# SCH_hiiiiibrahim_2025-10-19.net
KiCad netlist of a schematic drawn in EasyEDA
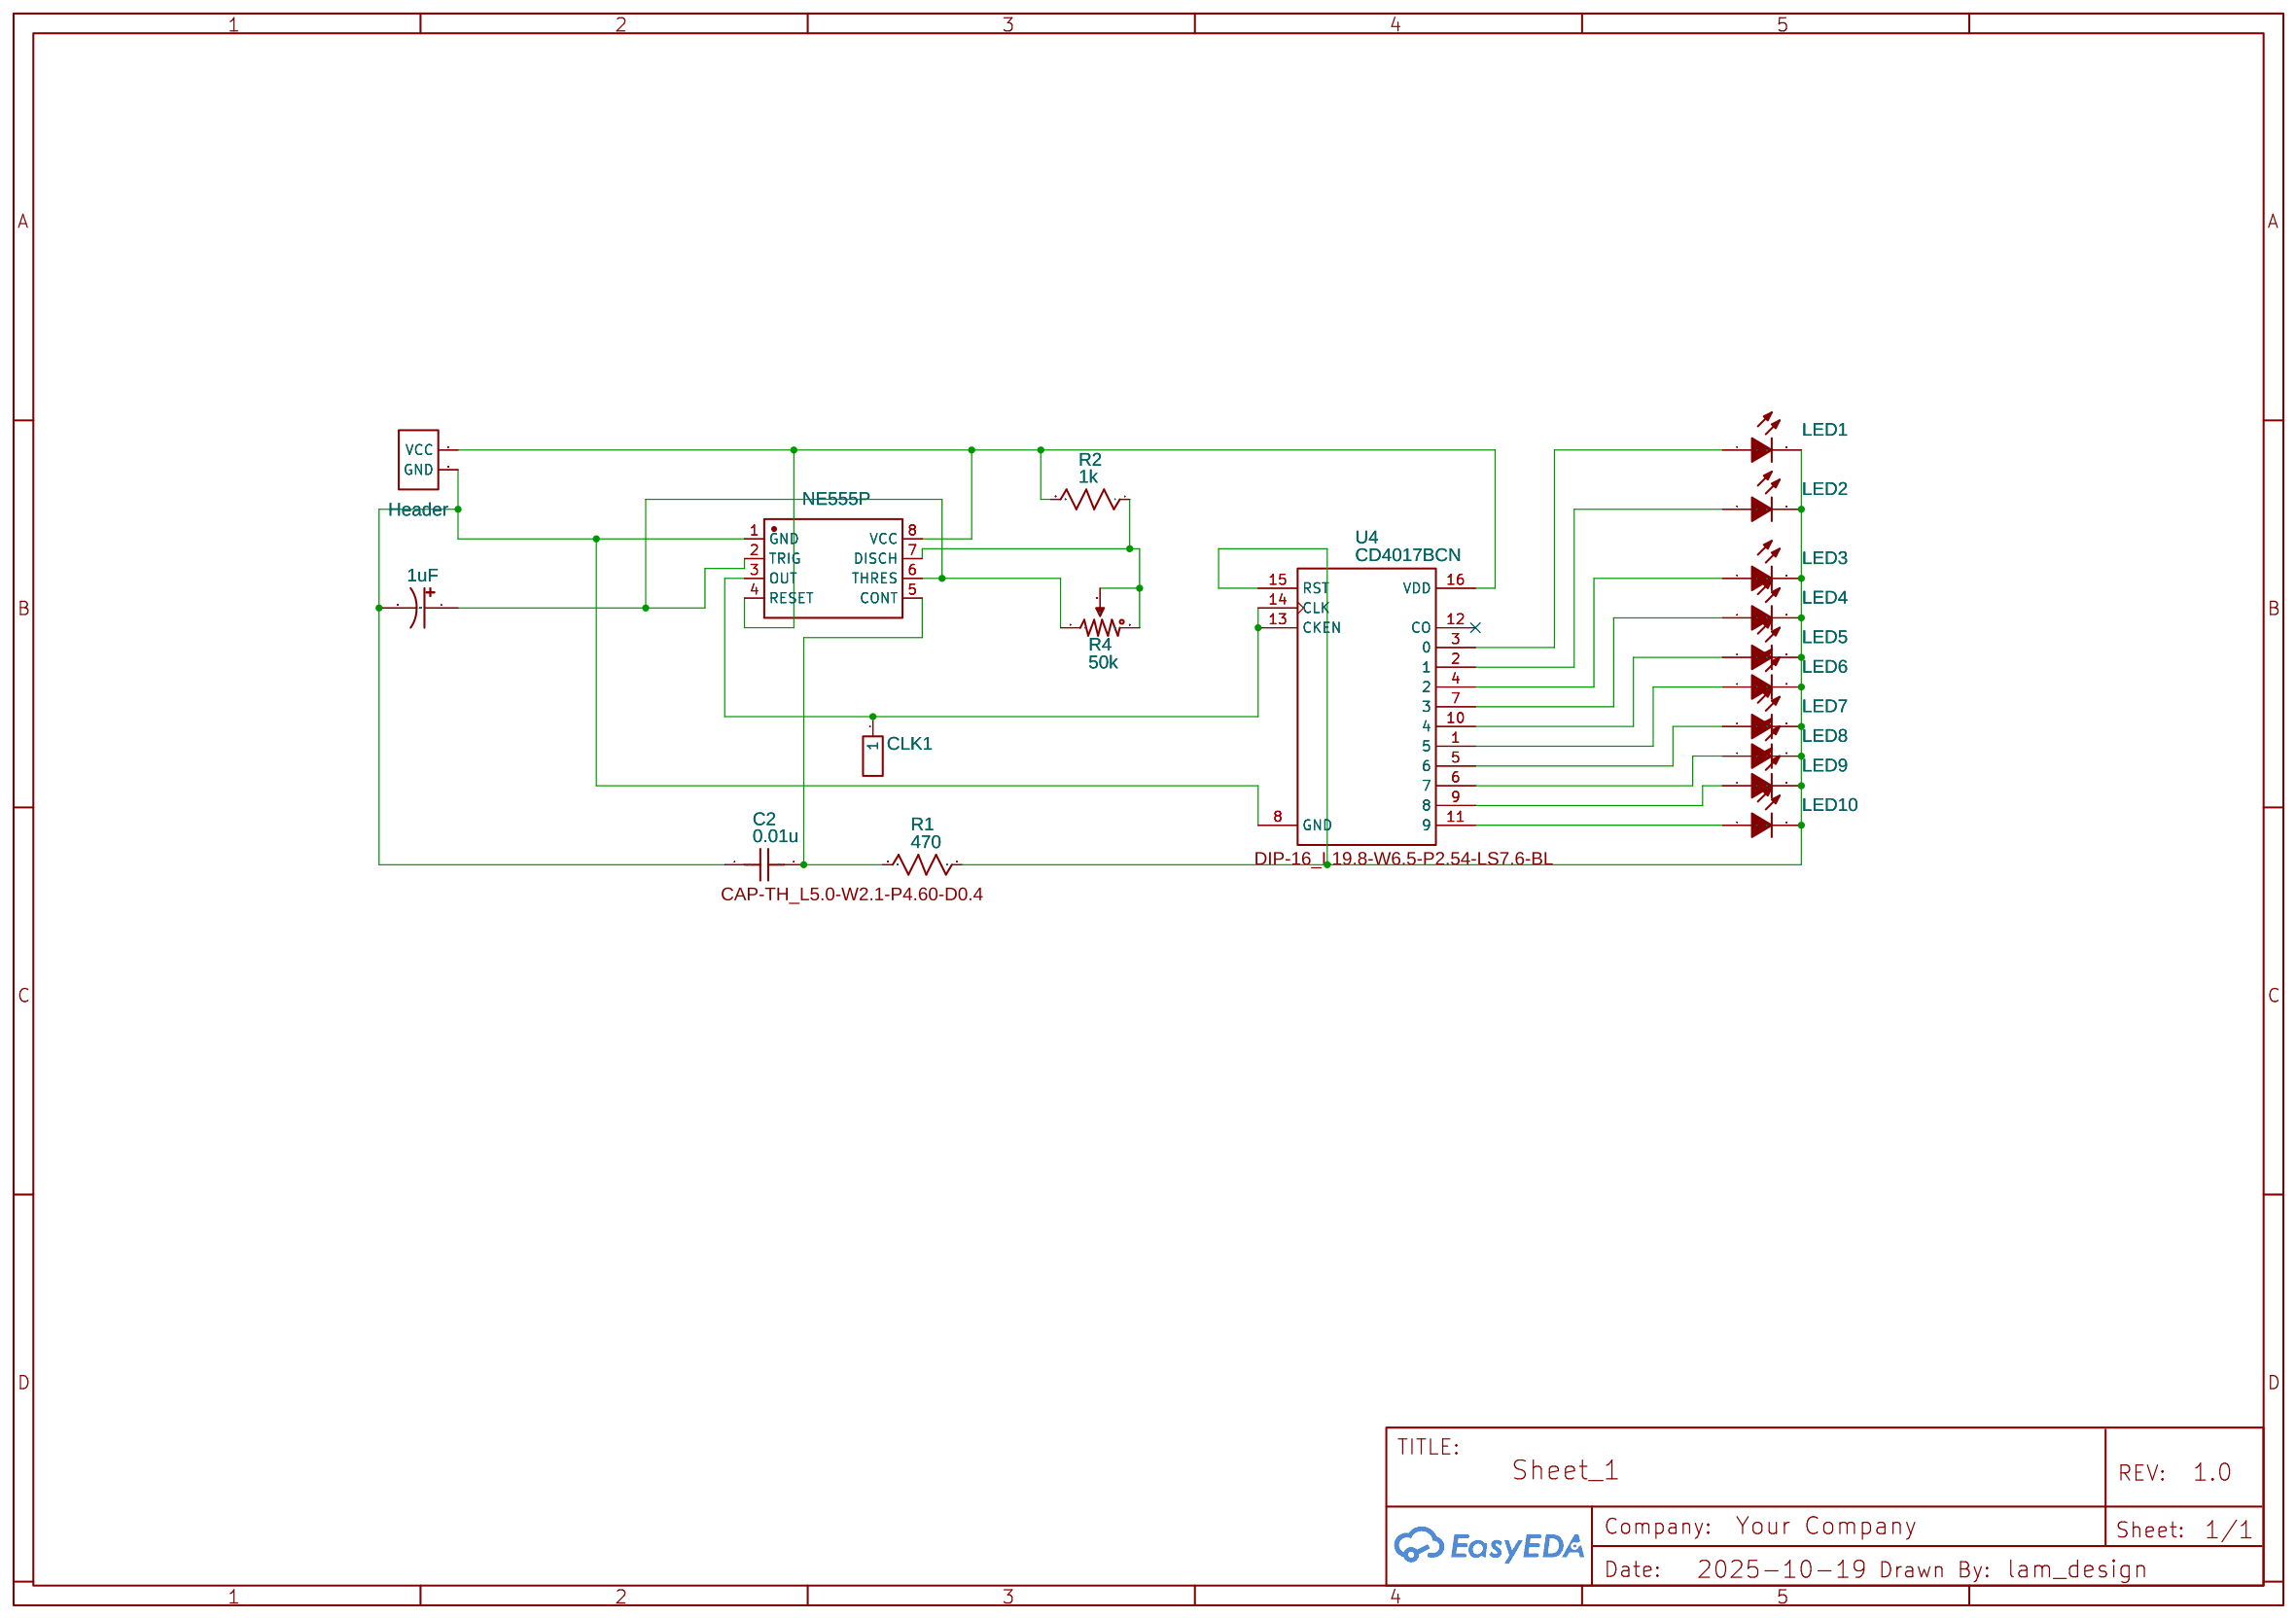
[diagram p0: schematic sheet]

(export (version "E")
  (design (tool "Eeschema 10.0.6"))
  (components
    (comp (ref "C1")
      (value "1uF")
      (fields (field (name "Manufacturer Part") "UVZ1H010MDD") (field (name "Manufacturer") "Nichicon(尼吉康)"))
      (libsource (lib "") (part "UVZ1H010MDD"))
    )
    (comp (ref "C2") (value "0.01u") (libsource (lib "") (part "C_0603_US")))
    (comp (ref "CLK1")
      (value "C81276")
      (fields
        (field (name "Manufacturer Part") "2.54-1*1P针")
        (field (name "Manufacturer") "BOOMELE(Boom Precision Elec)")
      )
      (libsource (lib "") (part "Header-Male-2.54_1x1"))
    )
    (comp (ref "H1") (value "Header") (libsource (lib "") (part "HEADER-FEMALE-2.54_1X2")))
    (comp (ref "LED1") (value "LED_5MM") (libsource (lib "") (part "LED_5MM")))
    (comp (ref "LED2") (value "LED_5MM") (libsource (lib "") (part "LED_5MM")))
    (comp (ref "LED3") (value "LED_5MM") (libsource (lib "") (part "LED_5MM")))
    (comp (ref "LED4") (value "LED_5MM") (libsource (lib "") (part "LED_5MM")))
    (comp (ref "LED5") (value "LED_5MM") (libsource (lib "") (part "LED_5MM")))
    (comp (ref "LED6") (value "LED_5MM") (libsource (lib "") (part "LED_5MM")))
    (comp (ref "LED7") (value "LED_5MM") (libsource (lib "") (part "LED_5MM")))
    (comp (ref "LED8") (value "LED_5MM") (libsource (lib "") (part "LED_5MM")))
    (comp (ref "LED9") (value "LED_5MM") (libsource (lib "") (part "LED_5MM")))
    (comp (ref "LED10") (value "LED_5MM") (libsource (lib "") (part "LED_5MM")))
    (comp (ref "R1")
      (value "470")
      (fields (field (name "Manufacturer Part") "?"))
      (libsource (lib "") (part "Resistor"))
    )
    (comp (ref "R2")
      (value "1k")
      (fields (field (name "Manufacturer Part") "?"))
      (libsource (lib "") (part "Resistor"))
    )
    (comp (ref "R4")
      (value "50k")
      (fields (field (name "Manufacturer Part") "?"))
      (libsource (lib "") (part "Potentiometer"))
    )
    (comp (ref "U2")
      (value "NE555P")
      (fields (field (name "Manufacturer") "TI(德州仪器)"))
      (libsource (lib "") (part "NE555P"))
    )
    (comp (ref "U4") (value "CD4017BCN") (libsource (lib "") (part "CD4017BCN")))
  )
  (nets
    (net (code "1") (name "Net-(H1-GND)") (class "Default")
      (node (ref "C1") (pin "2") (pinfunction "2_2") (pintype "unspecified"))
      (node (ref "C2") (pin "1") (pinfunction "1_1") (pintype "unspecified"))
      (node (ref "H1") (pin "2") (pinfunction "GND_2") (pintype "unspecified"))
      (node (ref "U2") (pin "1") (pinfunction "GND_1") (pintype "unspecified"))
      (node (ref "U4") (pin "8") (pinfunction "GND_8") (pintype "passive"))
    )
    (net (code "2") (name "Net-(H1-VCC)") (class "Default")
      (node (ref "H1") (pin "1") (pinfunction "VCC_1") (pintype "unspecified"))
      (node (ref "R2") (pin "2") (pinfunction "2_2") (pintype "unspecified"))
      (node (ref "U2") (pin "4") (pinfunction "RESET_4") (pintype "unspecified"))
      (node (ref "U2") (pin "8") (pinfunction "VCC_8") (pintype "unspecified"))
      (node (ref "U4") (pin "16") (pinfunction "VDD_16") (pintype "passive"))
    )
    (net (code "3") (name "Net-(LED1-A)") (class "Default")
      (node (ref "LED1") (pin "1") (pinfunction "A_1") (pintype "input"))
      (node (ref "U4") (pin "3") (pinfunction "0_3") (pintype "output"))
    )
    (net (code "4") (name "Net-(LED1-K)") (class "Default")
      (node (ref "LED1") (pin "2") (pinfunction "K_2") (pintype "input"))
      (node (ref "LED10") (pin "2") (pinfunction "K_2") (pintype "input"))
      (node (ref "LED2") (pin "2") (pinfunction "K_2") (pintype "input"))
      (node (ref "LED3") (pin "2") (pinfunction "K_2") (pintype "input"))
      (node (ref "LED4") (pin "2") (pinfunction "K_2") (pintype "input"))
      (node (ref "LED5") (pin "2") (pinfunction "K_2") (pintype "input"))
      (node (ref "LED6") (pin "2") (pinfunction "K_2") (pintype "input"))
      (node (ref "LED7") (pin "2") (pinfunction "K_2") (pintype "input"))
      (node (ref "LED8") (pin "2") (pinfunction "K_2") (pintype "input"))
      (node (ref "LED9") (pin "2") (pinfunction "K_2") (pintype "input"))
      (node (ref "R1") (pin "1") (pinfunction "1_1") (pintype "unspecified"))
      (node (ref "U4") (pin "15") (pinfunction "RST_15") (pintype "unspecified"))
    )
    (net (code "5") (name "Net-(LED2-A)") (class "Default")
      (node (ref "LED2") (pin "1") (pinfunction "A_1") (pintype "input"))
      (node (ref "U4") (pin "2") (pinfunction "1_2") (pintype "output"))
    )
    (net (code "6") (name "Net-(LED3-A)") (class "Default")
      (node (ref "LED3") (pin "1") (pinfunction "A_1") (pintype "input"))
      (node (ref "U4") (pin "4") (pinfunction "2_4") (pintype "output"))
    )
    (net (code "7") (name "Net-(LED4-A)") (class "Default")
      (node (ref "LED4") (pin "1") (pinfunction "A_1") (pintype "input"))
      (node (ref "U4") (pin "7") (pinfunction "3_7") (pintype "output"))
    )
    (net (code "8") (name "Net-(LED5-A)") (class "Default")
      (node (ref "LED5") (pin "1") (pinfunction "A_1") (pintype "input"))
      (node (ref "U4") (pin "10") (pinfunction "4_10") (pintype "output"))
    )
    (net (code "9") (name "Net-(LED6-A)") (class "Default")
      (node (ref "LED6") (pin "1") (pinfunction "A_1") (pintype "input"))
      (node (ref "U4") (pin "1") (pinfunction "5_1") (pintype "output"))
    )
    (net (code "10") (name "Net-(LED7-A)") (class "Default")
      (node (ref "LED7") (pin "1") (pinfunction "A_1") (pintype "input"))
      (node (ref "U4") (pin "5") (pinfunction "6_5") (pintype "output"))
    )
    (net (code "11") (name "Net-(LED8-A)") (class "Default")
      (node (ref "LED8") (pin "1") (pinfunction "A_1") (pintype "input"))
      (node (ref "U4") (pin "6") (pinfunction "7_6") (pintype "output"))
    )
    (net (code "12") (name "Net-(LED9-A)") (class "Default")
      (node (ref "LED9") (pin "1") (pinfunction "A_1") (pintype "input"))
      (node (ref "U4") (pin "9") (pinfunction "8_9") (pintype "output"))
    )
    (net (code "13") (name "Net-(LED10-A)") (class "Default")
      (node (ref "LED10") (pin "1") (pinfunction "A_1") (pintype "input"))
      (node (ref "U4") (pin "11") (pinfunction "9_11") (pintype "output"))
    )
    (net (code "14") (name "Net-(R4-2)") (class "Default")
      (node (ref "R2") (pin "1") (pinfunction "1_1") (pintype "unspecified"))
      (node (ref "R4") (pin "2") (pinfunction "3_2") (pintype "unspecified"))
      (node (ref "R4") (pin "3") (pinfunction "2_3") (pintype "unspecified"))
      (node (ref "U2") (pin "7") (pinfunction "DISCH_7") (pintype "unspecified"))
    )
    (net (code "15") (name "Net-(U2-CONT)") (class "Default")
      (node (ref "C2") (pin "2") (pinfunction "2_2") (pintype "unspecified"))
      (node (ref "R1") (pin "2") (pinfunction "2_2") (pintype "unspecified"))
      (node (ref "U2") (pin "5") (pinfunction "CONT_5") (pintype "unspecified"))
    )
    (net (code "16") (name "Net-(U2-OUT)") (class "Default")
      (node (ref "CLK1") (pin "1") (pinfunction "1_1") (pintype "unspecified"))
      (node (ref "U2") (pin "3") (pinfunction "OUT_3") (pintype "unspecified"))
      (node (ref "U4") (pin "13") (pinfunction "CKEN_13") (pintype "unspecified"))
      (node (ref "U4") (pin "14") (pinfunction "CLK_14") (pintype "unspecified"))
    )
    (net (code "17") (name "Net-(U2-THRES)") (class "Default")
      (node (ref "C1") (pin "1") (pinfunction "1_1") (pintype "unspecified"))
      (node (ref "R4") (pin "1") (pinfunction "1_1") (pintype "unspecified"))
      (node (ref "U2") (pin "2") (pinfunction "TRIG_2") (pintype "unspecified"))
      (node (ref "U2") (pin "6") (pinfunction "THRES_6") (pintype "unspecified"))
    )
    (net (code "18") (name "unconnected-(U4-CO-Pad12)") (class "Default")
      (node (ref "U4") (pin "12") (pinfunction "CO_12") (pintype "output+no_connect"))
    )
  )
)
